# 26_LMS3_RX2_BB_ADC.net
KiCad netlist of a schematic drawn in Altium Designer
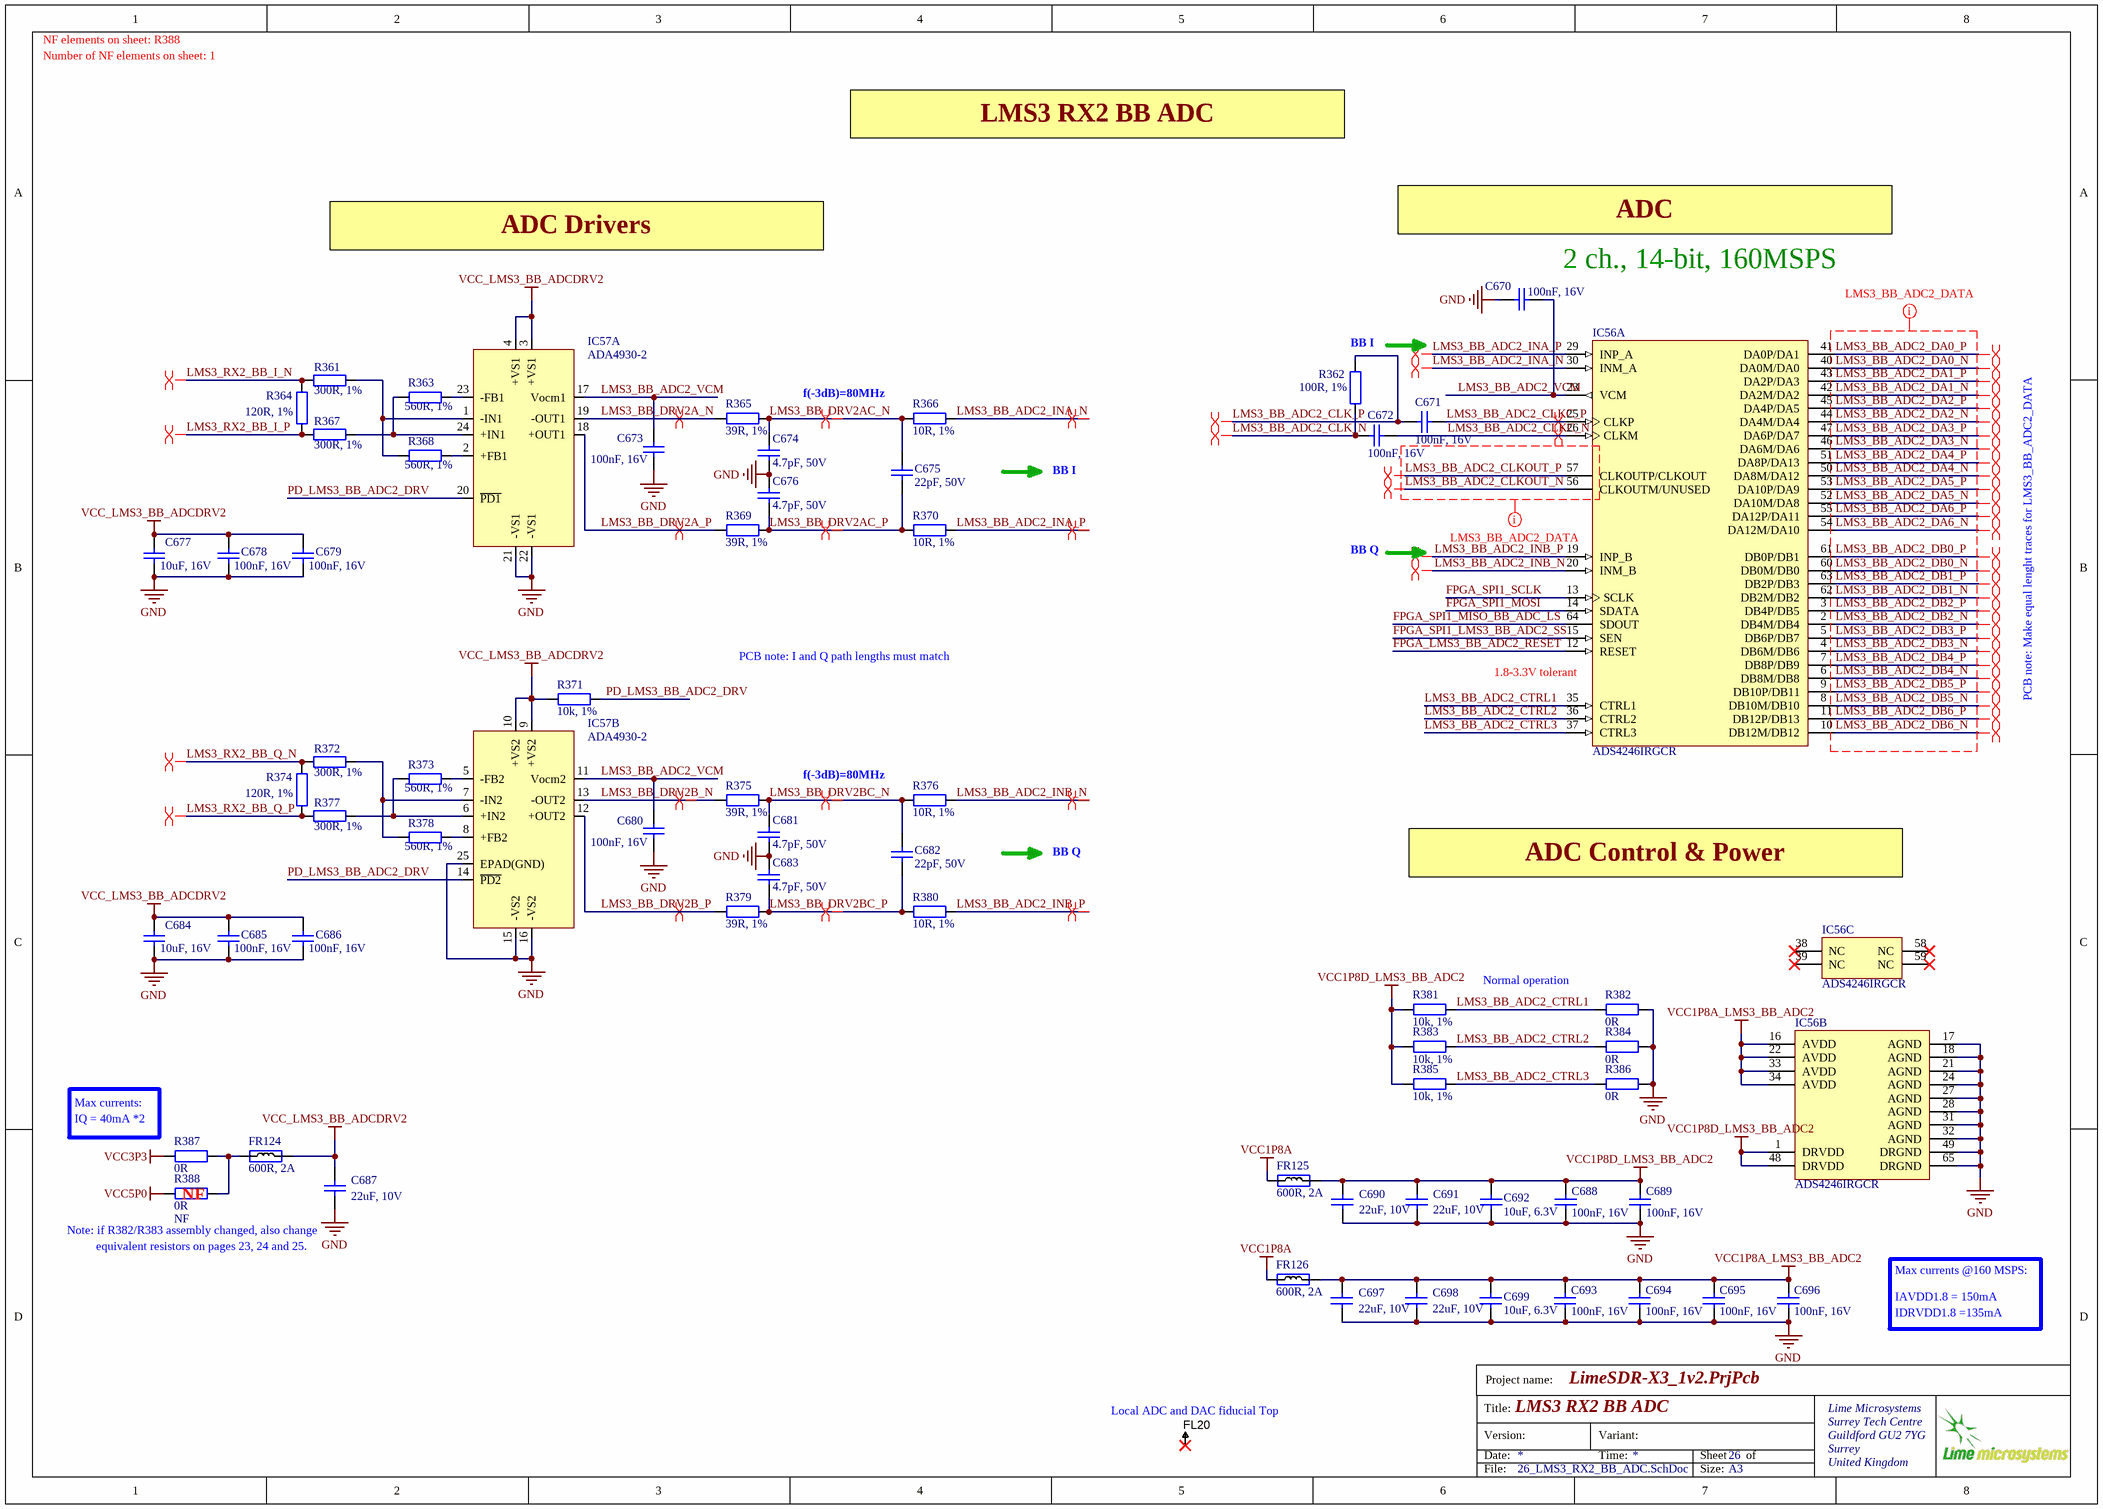
[diagram p0: 26_LMS3_RX2_BB_ADC.SchDoc]

(export (version "E")
  (design (tool "Eeschema 10.0.6"))
  (components
    (comp (ref "C670")
      (value "100nF, 16V")
      (footprint "CAP0402")
      (fields (field (name "TOLERANCE") "10 %") (field (name "MANUFACTURER") "Murata Electronics"))
      (libsource (lib "") (part "Cap_0603_3"))
    )
    (comp (ref "C671")
      (value "100nF, 16V")
      (footprint "CAP0402")
      (fields (field (name "TOLERANCE") "10 %") (field (name "MANUFACTURER") "Murata Electronics"))
      (libsource (lib "") (part "Cap_0603_3"))
    )
    (comp (ref "C672")
      (value "100nF, 16V")
      (footprint "CAP0402")
      (fields (field (name "TOLERANCE") "10 %") (field (name "MANUFACTURER") "Murata Electronics"))
      (libsource (lib "") (part "Cap_0603_5"))
    )
    (comp (ref "C673")
      (value "100nF, 16V")
      (footprint "CAP0402")
      (fields (field (name "TOLERANCE") "10 %") (field (name "MANUFACTURER") "Murata Electronics"))
      (libsource (lib "") (part "Cap_0603_5"))
    )
    (comp (ref "C674")
      (value "4.7pF, 50V")
      (footprint "CAP0402")
      (fields (field (name "MANUFACTURER") "MURATA"))
      (libsource (lib "LimeMicroAltiumLib_schLib") (part "Cap_0402"))
    )
    (comp (ref "C675")
      (value "22pF, 50V")
      (footprint "CAP0402")
      (fields (field (name "TOLERANCE") "±5%") (field (name "MANUFACTURER") "Yageo"))
      (libsource (lib "") (part "Cap_0402_1"))
    )
    (comp (ref "C676")
      (value "4.7pF, 50V")
      (footprint "CAP0402")
      (fields (field (name "MANUFACTURER") "MURATA"))
      (libsource (lib "LimeMicroAltiumLib_schLib") (part "Cap_0402"))
    )
    (comp (ref "C677")
      (value "10uF, 16V")
      (footprint "CAP0603")
      (fields (field (name "MANUFACTURER") "Yageo") (field (name "TOLERANCE") "±20%"))
      (libsource (lib "LimeMicroAltiumLib_schLib") (part "Cap_0603"))
    )
    (comp (ref "C678")
      (value "100nF, 16V")
      (footprint "CAP0402")
      (fields (field (name "TOLERANCE") "10 %") (field (name "MANUFACTURER") "Murata Electronics"))
      (libsource (lib "") (part "Cap_0603_5"))
    )
    (comp (ref "C679")
      (value "100nF, 16V")
      (footprint "CAP0402")
      (fields (field (name "TOLERANCE") "10 %") (field (name "MANUFACTURER") "Murata Electronics"))
      (libsource (lib "") (part "Cap_0603_5"))
    )
    (comp (ref "C680")
      (value "100nF, 16V")
      (footprint "CAP0402")
      (fields (field (name "TOLERANCE") "10 %") (field (name "MANUFACTURER") "Murata Electronics"))
      (libsource (lib "") (part "Cap_0603_6"))
    )
    (comp (ref "C681")
      (value "4.7pF, 50V")
      (footprint "CAP0402")
      (fields (field (name "MANUFACTURER") "MURATA"))
      (libsource (lib "LimeMicroAltiumLib_schLib") (part "Cap_0402"))
    )
    (comp (ref "C682")
      (value "22pF, 50V")
      (footprint "CAP0402")
      (fields (field (name "TOLERANCE") "±5%") (field (name "MANUFACTURER") "Yageo"))
      (libsource (lib "") (part "Cap_0402_1"))
    )
    (comp (ref "C683")
      (value "4.7pF, 50V")
      (footprint "CAP0402")
      (fields (field (name "MANUFACTURER") "MURATA"))
      (libsource (lib "LimeMicroAltiumLib_schLib") (part "Cap_0402"))
    )
    (comp (ref "C684")
      (value "10uF, 16V")
      (footprint "CAP0603")
      (fields (field (name "MANUFACTURER") "Yageo") (field (name "TOLERANCE") "±20%"))
      (libsource (lib "LimeMicroAltiumLib_schLib") (part "Cap_0603"))
    )
    (comp (ref "C685")
      (value "100nF, 16V")
      (footprint "CAP0402")
      (fields (field (name "TOLERANCE") "10 %") (field (name "MANUFACTURER") "Murata Electronics"))
      (libsource (lib "") (part "Cap_0603_5"))
    )
    (comp (ref "C686")
      (value "100nF, 16V")
      (footprint "CAP0402")
      (fields (field (name "TOLERANCE") "10 %") (field (name "MANUFACTURER") "Murata Electronics"))
      (libsource (lib "") (part "Cap_0603_5"))
    )
    (comp (ref "C687")
      (value "22uF, 10V")
      (footprint "CAP0603")
      (fields (field (name "TOLERANCE") "20 %") (field (name "MANUFACTURER") "TDK Corporation"))
      (libsource (lib "") (part "Cap_0603_2"))
    )
    (comp (ref "C688")
      (value "100nF, 16V")
      (footprint "CAP0402")
      (fields (field (name "TOLERANCE") "10 %") (field (name "MANUFACTURER") "Murata Electronics"))
      (libsource (lib "LimeFPGAboard_schLib") (part "Cap_0603"))
    )
    (comp (ref "C689")
      (value "100nF, 16V")
      (footprint "CAP0402")
      (fields (field (name "TOLERANCE") "10 %") (field (name "MANUFACTURER") "Murata Electronics"))
      (libsource (lib "LimeFPGAboard_schLib") (part "Cap_0603"))
    )
    (comp (ref "C690")
      (value "22uF, 10V")
      (footprint "CAP0603")
      (fields (field (name "TOLERANCE") "20 %") (field (name "MANUFACTURER") "TDK Corporation"))
      (libsource (lib "LimeFPGAboard_schLib") (part "Cap_0603"))
    )
    (comp (ref "C691")
      (value "22uF, 10V")
      (footprint "CAP0603")
      (fields (field (name "TOLERANCE") "20 %") (field (name "MANUFACTURER") "TDK Corporation"))
      (libsource (lib "LimeFPGAboard_schLib") (part "Cap_0603"))
    )
    (comp (ref "C692")
      (value "10uF, 6.3V")
      (footprint "CAP0603")
      (fields (field (name "TOLERANCE") "±20%") (field (name "MANUFACTURER") "Yageo"))
      (libsource (lib "") (part "Cap_0603_1"))
    )
    (comp (ref "C693")
      (value "100nF, 16V")
      (footprint "CAP0402")
      (fields (field (name "TOLERANCE") "10 %") (field (name "MANUFACTURER") "Murata Electronics"))
      (libsource (lib "") (part "Cap_0603_4"))
    )
    (comp (ref "C694")
      (value "100nF, 16V")
      (footprint "CAP0402")
      (fields (field (name "TOLERANCE") "10 %") (field (name "MANUFACTURER") "Murata Electronics"))
      (libsource (lib "") (part "Cap_0603_4"))
    )
    (comp (ref "C695")
      (value "100nF, 16V")
      (footprint "CAP0402")
      (fields (field (name "TOLERANCE") "10 %") (field (name "MANUFACTURER") "Murata Electronics"))
      (libsource (lib "") (part "Cap_0603_4"))
    )
    (comp (ref "C696")
      (value "100nF, 16V")
      (footprint "CAP0402")
      (fields (field (name "TOLERANCE") "10 %") (field (name "MANUFACTURER") "Murata Electronics"))
      (libsource (lib "") (part "Cap_0603_4"))
    )
    (comp (ref "C697")
      (value "22uF, 10V")
      (footprint "CAP0603")
      (fields (field (name "TOLERANCE") "20 %") (field (name "MANUFACTURER") "TDK Corporation"))
      (libsource (lib "") (part "Cap_0603_4"))
    )
    (comp (ref "C698")
      (value "22uF, 10V")
      (footprint "CAP0603")
      (fields (field (name "TOLERANCE") "20 %") (field (name "MANUFACTURER") "TDK Corporation"))
      (libsource (lib "") (part "Cap_0603_4"))
    )
    (comp (ref "C699")
      (value "10uF, 6.3V")
      (footprint "CAP0603")
      (fields (field (name "TOLERANCE") "±20%") (field (name "MANUFACTURER") "Yageo"))
      (libsource (lib "") (part "Cap_0603_7"))
    )
    (comp (ref "FL20")
      (value "Fiducial")
      (footprint "Fiducial_local")
      (libsource (lib "LimeMicroAltiumLib_schLib") (part "Fiducial"))
    )
    (comp (ref "FR124")
      (value "600R, 2A")
      (footprint "RES0805")
      (fields (field (name "MANUFACTURER") "TDK Corporation"))
      (libsource (lib "LimeMicroAltiumLib_schLib") (part "Ferrite"))
    )
    (comp (ref "FR125")
      (value "600R, 2A")
      (footprint "RES0805")
      (fields (field (name "MANUFACTURER") "TDK Corporation"))
      (libsource (lib "LimeFPGAboard_schLib") (part "Ferrite"))
    )
    (comp (ref "FR126")
      (value "600R, 2A")
      (footprint "RES0805")
      (fields (field (name "MANUFACTURER") "TDK Corporation"))
      (libsource (lib "LimeFPGAboard_schLib") (part "Ferrite"))
    )
    (comp (ref "IC56")
      (value "ADS4246IRGCR")
      (footprint "TI-RGC64-7400X7400TP_V")
      (description "14-Bit 160 MSPS Dual Low Power ADC, -40 to 85 degC, 64-pin QFN (RGC64), Green (RoHS & no Sb/Br)")
      (fields (field (name "MANUFACTURER") "Texas Instruments"))
      (libsource (lib "LimeMicroAltiumLib_schLib") (part "ADS4246IRGCR"))
    )
    (comp (ref "IC57")
      (value "ADA4930-2")
      (footprint "ADA4930-2_LFCSP-24")
      (fields (field (name "MANUFACTURER") "Analog Devices Inc."))
      (libsource (lib "LimeMicroAltiumLib_schLib") (part "ADA4930-2"))
    )
    (comp (ref "R361")
      (value "300R, 1%")
      (footprint "RES0402")
      (fields (field (name "TOLERANCE") "±1%") (field (name "MANUFACTURER") "Vishay Dale"))
      (libsource (lib "") (part "Res_0402_1"))
    )
    (comp (ref "R362")
      (value "100R, 1%")
      (footprint "RES0402")
      (fields (field (name "TOLERANCE") "±1%") (field (name "MANUFACTURER") "Stackpole Electronics Inc."))
      (libsource (lib "") (part "Res_0402_1"))
    )
    (comp (ref "R363")
      (value "560R, 1%")
      (footprint "RES0402")
      (fields (field (name "TOLERANCE") "±1%") (field (name "MANUFACTURER") "Vishay Dale"))
      (libsource (lib "") (part "Res_0402_1"))
    )
    (comp (ref "R364")
      (value "120R, 1%")
      (footprint "RES0402")
      (fields (field (name "MANUFACTURER") "Yageo") (field (name "TOLERANCE") "1%"))
      (libsource (lib "LimeFPGAboard_schLib") (part "Res_0402"))
    )
    (comp (ref "R365")
      (value "39R, 1%")
      (footprint "RES0402")
      (fields (field (name "MANUFACTURER") "Yageo") (field (name "TOLERANCE") "1%"))
      (libsource (lib "LimeMicroAltiumLib_schLib") (part "Res_0402"))
    )
    (comp (ref "R366")
      (value "10R, 1%")
      (footprint "RES0402")
      (fields (field (name "TOLERANCE") "1%"))
      (libsource (lib "LimeMicroAltiumLib_schLib") (part "Res_0402"))
    )
    (comp (ref "R367")
      (value "300R, 1%")
      (footprint "RES0402")
      (fields (field (name "TOLERANCE") "±1%") (field (name "MANUFACTURER") "Vishay Dale"))
      (libsource (lib "") (part "Res_0402_1"))
    )
    (comp (ref "R368")
      (value "560R, 1%")
      (footprint "RES0402")
      (fields (field (name "TOLERANCE") "±1%") (field (name "MANUFACTURER") "Vishay Dale"))
      (libsource (lib "") (part "Res_0402_1"))
    )
    (comp (ref "R369")
      (value "39R, 1%")
      (footprint "RES0402")
      (fields (field (name "MANUFACTURER") "Yageo") (field (name "TOLERANCE") "1%"))
      (libsource (lib "LimeMicroAltiumLib_schLib") (part "Res_0402"))
    )
    (comp (ref "R370")
      (value "10R, 1%")
      (footprint "RES0402")
      (fields (field (name "TOLERANCE") "1%"))
      (libsource (lib "LimeMicroAltiumLib_schLib") (part "Res_0402"))
    )
    (comp (ref "R371")
      (value "10k, 1%")
      (footprint "RES0402")
      (fields (field (name "MANUFACTURER") "Yageo") (field (name "TOLERANCE") "±1%"))
      (libsource (lib "LimeMicroAltiumLib_schLib") (part "Res_0402"))
    )
    (comp (ref "R372")
      (value "300R, 1%")
      (footprint "RES0402")
      (fields (field (name "TOLERANCE") "±1%") (field (name "MANUFACTURER") "Vishay Dale"))
      (libsource (lib "") (part "Res_0402_1"))
    )
    (comp (ref "R373")
      (value "560R, 1%")
      (footprint "RES0402")
      (fields (field (name "TOLERANCE") "±1%") (field (name "MANUFACTURER") "Vishay Dale"))
      (libsource (lib "") (part "Res_0402_1"))
    )
    (comp (ref "R374")
      (value "120R, 1%")
      (footprint "RES0402")
      (fields (field (name "MANUFACTURER") "Yageo") (field (name "TOLERANCE") "1%"))
      (libsource (lib "LimeFPGAboard_schLib") (part "Res_0402"))
    )
    (comp (ref "R375")
      (value "39R, 1%")
      (footprint "RES0402")
      (fields (field (name "MANUFACTURER") "Yageo") (field (name "TOLERANCE") "1%"))
      (libsource (lib "LimeMicroAltiumLib_schLib") (part "Res_0402"))
    )
    (comp (ref "R376")
      (value "10R, 1%")
      (footprint "RES0402")
      (fields (field (name "TOLERANCE") "1%"))
      (libsource (lib "LimeMicroAltiumLib_schLib") (part "Res_0402"))
    )
    (comp (ref "R377")
      (value "300R, 1%")
      (footprint "RES0402")
      (fields (field (name "TOLERANCE") "±1%") (field (name "MANUFACTURER") "Vishay Dale"))
      (libsource (lib "") (part "Res_0402_1"))
    )
    (comp (ref "R378")
      (value "560R, 1%")
      (footprint "RES0402")
      (fields (field (name "TOLERANCE") "±1%") (field (name "MANUFACTURER") "Vishay Dale"))
      (libsource (lib "") (part "Res_0402_1"))
    )
    (comp (ref "R379")
      (value "39R, 1%")
      (footprint "RES0402")
      (fields (field (name "MANUFACTURER") "Yageo") (field (name "TOLERANCE") "1%"))
      (libsource (lib "LimeMicroAltiumLib_schLib") (part "Res_0402"))
    )
    (comp (ref "R380")
      (value "10R, 1%")
      (footprint "RES0402")
      (fields (field (name "TOLERANCE") "1%"))
      (libsource (lib "LimeMicroAltiumLib_schLib") (part "Res_0402"))
    )
    (comp (ref "R381")
      (value "10k, 1%")
      (footprint "RES0402")
      (fields (field (name "MANUFACTURER") "Yageo") (field (name "TOLERANCE") "±1%"))
      (libsource (lib "LimeMicroAltiumLib_schLib") (part "Res_0402"))
    )
    (comp (ref "R382")
      (value "0R")
      (footprint "RES0402")
      (fields (field (name "MANUFACTURER") "Yageo"))
      (libsource (lib "") (part "Res_0402_1"))
    )
    (comp (ref "R383")
      (value "10k, 1%")
      (footprint "RES0402")
      (fields (field (name "MANUFACTURER") "Yageo") (field (name "TOLERANCE") "±1%"))
      (libsource (lib "LimeMicroAltiumLib_schLib") (part "Res_0402"))
    )
    (comp (ref "R384")
      (value "0R")
      (footprint "RES0402")
      (fields (field (name "MANUFACTURER") "Yageo"))
      (libsource (lib "") (part "Res_0402_1"))
    )
    (comp (ref "R385")
      (value "10k, 1%")
      (footprint "RES0402")
      (fields (field (name "MANUFACTURER") "Yageo") (field (name "TOLERANCE") "±1%"))
      (libsource (lib "LimeMicroAltiumLib_schLib") (part "Res_0402"))
    )
    (comp (ref "R386")
      (value "0R")
      (footprint "RES0402")
      (fields (field (name "MANUFACTURER") "Yageo"))
      (libsource (lib "") (part "Res_0402_1"))
    )
    (comp (ref "R387")
      (value "0R")
      (footprint "RES0402")
      (fields (field (name "MANUFACTURER") "Yageo") (field (name "TOLERANCE") "Jumper"))
      (libsource (lib "LimeMicroAltiumLib_schLib") (part "Res_0402"))
    )
    (comp (ref "R388")
      (value "0R")
      (footprint "RES0402")
      (fields
        (field (name "ASSEMBLY INFO") "NF")
        (field (name "MANUFACTURER") "Yageo")
        (field (name "TOLERANCE") "Jumper")
      )
      (libsource (lib "LimeMicroAltiumLib_schLib") (part "Res_0402"))
    )
  )
  (nets
    (net (code "1") (name "/FPGA_LMS3_BB_ADC2_RESET") (class "Default")
      (node (ref "IC56") (pin "12") (pinfunction "RESET_12") (pintype "input"))
    )
    (net (code "2") (name "/FPGA_SPI1_LMS3_BB_ADC2_SS") (class "Default")
      (node (ref "IC56") (pin "15") (pinfunction "SEN_15") (pintype "input"))
    )
    (net (code "3") (name "/FPGA_SPI1_MISO_BB_ADC_LS") (class "Default")
      (node (ref "IC56") (pin "64") (pinfunction "SDOUT_64") (pintype "tri_state"))
    )
    (net (code "4") (name "/FPGA_SPI1_MOSI") (class "Default")
      (node (ref "IC56") (pin "14") (pinfunction "SDATA_14") (pintype "input"))
    )
    (net (code "5") (name "/FPGA_SPI1_SCLK") (class "Default")
      (node (ref "IC56") (pin "13") (pinfunction "SCLK_13") (pintype "input"))
    )
    (net (code "6") (name "/LMS3_BB_ADC2_CLKC_N") (class "Default")
      (node (ref "C672") (pin "1") (pinfunction "1_1") (pintype "passive"))
      (node (ref "IC56") (pin "26") (pinfunction "CLKM_26") (pintype "input"))
    )
    (net (code "7") (name "/LMS3_BB_ADC2_CLKC_P") (class "Default")
      (node (ref "C671") (pin "1") (pinfunction "1_1") (pintype "passive"))
      (node (ref "IC56") (pin "25") (pinfunction "CLKP_25") (pintype "input"))
    )
    (net (code "8") (name "/LMS3_BB_ADC2_CLKOUT_N") (class "Default")
      (node (ref "IC56") (pin "56") (pinfunction "CLKOUTM/UNUSED_56") (pintype "tri_state"))
    )
    (net (code "9") (name "/LMS3_BB_ADC2_CLKOUT_P") (class "Default")
      (node (ref "IC56") (pin "57") (pinfunction "CLKOUTP/CLKOUT_57") (pintype "tri_state"))
    )
    (net (code "10") (name "/LMS3_BB_ADC2_CLK_N") (class "Default")
      (node (ref "C672") (pin "2") (pinfunction "2_2") (pintype "passive"))
      (node (ref "R362") (pin "1") (pinfunction "1_1") (pintype "passive"))
    )
    (net (code "11") (name "/LMS3_BB_ADC2_CLK_P") (class "Default")
      (node (ref "C671") (pin "2") (pinfunction "2_2") (pintype "passive"))
      (node (ref "R362") (pin "2") (pinfunction "2_2") (pintype "passive"))
    )
    (net (code "12") (name "/LMS3_BB_ADC2_CTRL1") (class "Default")
      (node (ref "IC56") (pin "35") (pinfunction "CTRL1_35") (pintype "input"))
      (node (ref "R381") (pin "1") (pinfunction "1_1") (pintype "passive"))
      (node (ref "R382") (pin "2") (pinfunction "2_2") (pintype "passive"))
    )
    (net (code "13") (name "/LMS3_BB_ADC2_CTRL2") (class "Default")
      (node (ref "IC56") (pin "36") (pinfunction "CTRL2_36") (pintype "input"))
      (node (ref "R383") (pin "1") (pinfunction "1_1") (pintype "passive"))
      (node (ref "R384") (pin "2") (pinfunction "2_2") (pintype "passive"))
    )
    (net (code "14") (name "/LMS3_BB_ADC2_CTRL3") (class "Default")
      (node (ref "IC56") (pin "37") (pinfunction "CTRL3_37") (pintype "input"))
      (node (ref "R385") (pin "1") (pinfunction "1_1") (pintype "passive"))
      (node (ref "R386") (pin "2") (pinfunction "2_2") (pintype "passive"))
    )
    (net (code "15") (name "/LMS3_BB_ADC2_DA0_N") (class "Default")
      (node (ref "IC56") (pin "40") (pinfunction "DA0M/DA0_40") (pintype "tri_state"))
    )
    (net (code "16") (name "/LMS3_BB_ADC2_DA0_P") (class "Default")
      (node (ref "IC56") (pin "41") (pinfunction "DA0P/DA1_41") (pintype "tri_state"))
    )
    (net (code "17") (name "/LMS3_BB_ADC2_DA1_N") (class "Default")
      (node (ref "IC56") (pin "42") (pinfunction "DA2M/DA2_42") (pintype "tri_state"))
    )
    (net (code "18") (name "/LMS3_BB_ADC2_DA1_P") (class "Default")
      (node (ref "IC56") (pin "43") (pinfunction "DA2P/DA3_43") (pintype "tri_state"))
    )
    (net (code "19") (name "/LMS3_BB_ADC2_DA2_N") (class "Default")
      (node (ref "IC56") (pin "44") (pinfunction "DA4M/DA4_44") (pintype "tri_state"))
    )
    (net (code "20") (name "/LMS3_BB_ADC2_DA2_P") (class "Default")
      (node (ref "IC56") (pin "45") (pinfunction "DA4P/DA5_45") (pintype "tri_state"))
    )
    (net (code "21") (name "/LMS3_BB_ADC2_DA3_N") (class "Default")
      (node (ref "IC56") (pin "46") (pinfunction "DA6M/DA6_46") (pintype "tri_state"))
    )
    (net (code "22") (name "/LMS3_BB_ADC2_DA3_P") (class "Default")
      (node (ref "IC56") (pin "47") (pinfunction "DA6P/DA7_47") (pintype "tri_state"))
    )
    (net (code "23") (name "/LMS3_BB_ADC2_DA4_N") (class "Default")
      (node (ref "IC56") (pin "50") (pinfunction "DA8M/DA12_50") (pintype "tri_state"))
    )
    (net (code "24") (name "/LMS3_BB_ADC2_DA4_P") (class "Default")
      (node (ref "IC56") (pin "51") (pinfunction "DA8P/DA13_51") (pintype "tri_state"))
    )
    (net (code "25") (name "/LMS3_BB_ADC2_DA5_N") (class "Default")
      (node (ref "IC56") (pin "52") (pinfunction "DA10M/DA8_52") (pintype "tri_state"))
    )
    (net (code "26") (name "/LMS3_BB_ADC2_DA5_P") (class "Default")
      (node (ref "IC56") (pin "53") (pinfunction "DA10P/DA9_53") (pintype "tri_state"))
    )
    (net (code "27") (name "/LMS3_BB_ADC2_DA6_N") (class "Default")
      (node (ref "IC56") (pin "54") (pinfunction "DA12M/DA10_54") (pintype "tri_state"))
    )
    (net (code "28") (name "/LMS3_BB_ADC2_DA6_P") (class "Default")
      (node (ref "IC56") (pin "55") (pinfunction "DA12P/DA11_55") (pintype "tri_state"))
    )
    (net (code "29") (name "/LMS3_BB_ADC2_DB0_N") (class "Default")
      (node (ref "IC56") (pin "60") (pinfunction "DB0M/DB0_60") (pintype "tri_state"))
    )
    (net (code "30") (name "/LMS3_BB_ADC2_DB0_P") (class "Default")
      (node (ref "IC56") (pin "61") (pinfunction "DB0P/DB1_61") (pintype "tri_state"))
    )
    (net (code "31") (name "/LMS3_BB_ADC2_DB1_N") (class "Default")
      (node (ref "IC56") (pin "62") (pinfunction "DB2M/DB2_62") (pintype "tri_state"))
    )
    (net (code "32") (name "/LMS3_BB_ADC2_DB1_P") (class "Default")
      (node (ref "IC56") (pin "63") (pinfunction "DB2P/DB3_63") (pintype "tri_state"))
    )
    (net (code "33") (name "/LMS3_BB_ADC2_DB2_N") (class "Default")
      (node (ref "IC56") (pin "2") (pinfunction "DB4M/DB4_2") (pintype "tri_state"))
    )
    (net (code "34") (name "/LMS3_BB_ADC2_DB2_P") (class "Default")
      (node (ref "IC56") (pin "3") (pinfunction "DB4P/DB5_3") (pintype "tri_state"))
    )
    (net (code "35") (name "/LMS3_BB_ADC2_DB3_N") (class "Default")
      (node (ref "IC56") (pin "4") (pinfunction "DB6M/DB6_4") (pintype "tri_state"))
    )
    (net (code "36") (name "/LMS3_BB_ADC2_DB3_P") (class "Default")
      (node (ref "IC56") (pin "5") (pinfunction "DB6P/DB7_5") (pintype "tri_state"))
    )
    (net (code "37") (name "/LMS3_BB_ADC2_DB4_N") (class "Default")
      (node (ref "IC56") (pin "6") (pinfunction "DB8M/DB8_6") (pintype "tri_state"))
    )
    (net (code "38") (name "/LMS3_BB_ADC2_DB4_P") (class "Default")
      (node (ref "IC56") (pin "7") (pinfunction "DB8P/DB9_7") (pintype "tri_state"))
    )
    (net (code "39") (name "/LMS3_BB_ADC2_DB5_N") (class "Default")
      (node (ref "IC56") (pin "8") (pinfunction "DB10M/DB10_8") (pintype "tri_state"))
    )
    (net (code "40") (name "/LMS3_BB_ADC2_DB5_P") (class "Default")
      (node (ref "IC56") (pin "9") (pinfunction "DB10P/DB11_9") (pintype "tri_state"))
    )
    (net (code "41") (name "/LMS3_BB_ADC2_DB6_N") (class "Default")
      (node (ref "IC56") (pin "10") (pinfunction "DB12M/DB12_10") (pintype "tri_state"))
    )
    (net (code "42") (name "/LMS3_BB_ADC2_DB6_P") (class "Default")
      (node (ref "IC56") (pin "11") (pinfunction "DB12P/DB13_11") (pintype "tri_state"))
    )
    (net (code "43") (name "/LMS3_BB_ADC2_INA_N") (class "Default")
      (node (ref "IC56") (pin "30") (pinfunction "INM_A_30") (pintype "input"))
      (node (ref "R366") (pin "1") (pinfunction "1_1") (pintype "passive"))
    )
    (net (code "44") (name "/LMS3_BB_ADC2_INA_P") (class "Default")
      (node (ref "IC56") (pin "29") (pinfunction "INP_A_29") (pintype "input"))
      (node (ref "R370") (pin "1") (pinfunction "1_1") (pintype "passive"))
    )
    (net (code "45") (name "/LMS3_BB_ADC2_INB_N") (class "Default")
      (node (ref "IC56") (pin "20") (pinfunction "INM_B_20") (pintype "input"))
      (node (ref "R376") (pin "1") (pinfunction "1_1") (pintype "passive"))
    )
    (net (code "46") (name "/LMS3_BB_ADC2_INB_P") (class "Default")
      (node (ref "IC56") (pin "19") (pinfunction "INP_B_19") (pintype "input"))
      (node (ref "R380") (pin "1") (pinfunction "1_1") (pintype "passive"))
    )
    (net (code "47") (name "/LMS3_BB_ADC2_VCM") (class "Default")
      (node (ref "C670") (pin "2") (pinfunction "2_2") (pintype "passive"))
      (node (ref "C673") (pin "1") (pinfunction "1_1") (pintype "passive"))
      (node (ref "C680") (pin "1") (pinfunction "1_1") (pintype "passive"))
      (node (ref "IC56") (pin "23") (pinfunction "VCM_23") (pintype "output"))
      (node (ref "IC57") (pin "11") (pinfunction "Vocm2_11") (pintype "input"))
      (node (ref "IC57") (pin "17") (pinfunction "Vocm1_17") (pintype "input"))
    )
    (net (code "48") (name "/LMS3_BB_DRV2AC_N") (class "Default")
      (node (ref "C674") (pin "1") (pinfunction "1_1") (pintype "passive"))
      (node (ref "C675") (pin "1") (pinfunction "1_1") (pintype "passive"))
      (node (ref "R365") (pin "1") (pinfunction "1_1") (pintype "passive"))
      (node (ref "R366") (pin "2") (pinfunction "2_2") (pintype "passive"))
    )
    (net (code "49") (name "/LMS3_BB_DRV2AC_P") (class "Default")
      (node (ref "C675") (pin "2") (pinfunction "2_2") (pintype "passive"))
      (node (ref "C676") (pin "2") (pinfunction "2_2") (pintype "passive"))
      (node (ref "R369") (pin "1") (pinfunction "1_1") (pintype "passive"))
      (node (ref "R370") (pin "2") (pinfunction "2_2") (pintype "passive"))
    )
    (net (code "50") (name "/LMS3_BB_DRV2A_N") (class "Default")
      (node (ref "IC57") (pin "19") (pinfunction "-OUT1_19") (pintype "output"))
      (node (ref "R365") (pin "2") (pinfunction "2_2") (pintype "passive"))
    )
    (net (code "51") (name "/LMS3_BB_DRV2A_P") (class "Default")
      (node (ref "IC57") (pin "18") (pinfunction "+OUT1_18") (pintype "output"))
      (node (ref "R369") (pin "2") (pinfunction "2_2") (pintype "passive"))
    )
    (net (code "52") (name "/LMS3_BB_DRV2BC_N") (class "Default")
      (node (ref "C681") (pin "1") (pinfunction "1_1") (pintype "passive"))
      (node (ref "C682") (pin "1") (pinfunction "1_1") (pintype "passive"))
      (node (ref "R375") (pin "1") (pinfunction "1_1") (pintype "passive"))
      (node (ref "R376") (pin "2") (pinfunction "2_2") (pintype "passive"))
    )
    (net (code "53") (name "/LMS3_BB_DRV2BC_P") (class "Default")
      (node (ref "C682") (pin "2") (pinfunction "2_2") (pintype "passive"))
      (node (ref "C683") (pin "2") (pinfunction "2_2") (pintype "passive"))
      (node (ref "R379") (pin "1") (pinfunction "1_1") (pintype "passive"))
      (node (ref "R380") (pin "2") (pinfunction "2_2") (pintype "passive"))
    )
    (net (code "54") (name "/LMS3_BB_DRV2B_N") (class "Default")
      (node (ref "IC57") (pin "13") (pinfunction "-OUT2_13") (pintype "output"))
      (node (ref "R375") (pin "2") (pinfunction "2_2") (pintype "passive"))
    )
    (net (code "55") (name "/LMS3_BB_DRV2B_P") (class "Default")
      (node (ref "IC57") (pin "12") (pinfunction "+OUT2_12") (pintype "output"))
      (node (ref "R379") (pin "2") (pinfunction "2_2") (pintype "passive"))
    )
    (net (code "56") (name "/LMS3_RX2_BB_I_N") (class "Default")
      (node (ref "R361") (pin "2") (pinfunction "2_2") (pintype "passive"))
      (node (ref "R364") (pin "2") (pinfunction "2_2") (pintype "passive"))
    )
    (net (code "57") (name "/LMS3_RX2_BB_I_P") (class "Default")
      (node (ref "R364") (pin "1") (pinfunction "1_1") (pintype "passive"))
      (node (ref "R367") (pin "2") (pinfunction "2_2") (pintype "passive"))
    )
    (net (code "58") (name "/LMS3_RX2_BB_Q_N") (class "Default")
      (node (ref "R372") (pin "2") (pinfunction "2_2") (pintype "passive"))
      (node (ref "R374") (pin "2") (pinfunction "2_2") (pintype "passive"))
    )
    (net (code "59") (name "/LMS3_RX2_BB_Q_P") (class "Default")
      (node (ref "R374") (pin "1") (pinfunction "1_1") (pintype "passive"))
      (node (ref "R377") (pin "2") (pinfunction "2_2") (pintype "passive"))
    )
    (net (code "60") (name "/PD_LMS3_BB_ADC2_DRV") (class "Default")
      (node (ref "IC57") (pin "14") (pinfunction "~{PD2}_14") (pintype "input"))
      (node (ref "IC57") (pin "20") (pinfunction "~{PD1}_20") (pintype "input"))
      (node (ref "R371") (pin "1") (pinfunction "1_1") (pintype "passive"))
    )
    (net (code "61") (name "GND") (class "Default")
      (node (ref "C670") (pin "1") (pinfunction "1_1") (pintype "passive"))
      (node (ref "C673") (pin "2") (pinfunction "2_2") (pintype "passive"))
      (node (ref "C674") (pin "2") (pinfunction "2_2") (pintype "passive"))
      (node (ref "C676") (pin "1") (pinfunction "1_1") (pintype "passive"))
      (node (ref "C677") (pin "1") (pinfunction "1_1") (pintype "passive"))
      (node (ref "C678") (pin "2") (pinfunction "2_2") (pintype "passive"))
      (node (ref "C679") (pin "2") (pinfunction "2_2") (pintype "passive"))
      (node (ref "C680") (pin "2") (pinfunction "2_2") (pintype "passive"))
      (node (ref "C681") (pin "2") (pinfunction "2_2") (pintype "passive"))
      (node (ref "C683") (pin "1") (pinfunction "1_1") (pintype "passive"))
      (node (ref "C684") (pin "1") (pinfunction "1_1") (pintype "passive"))
      (node (ref "C685") (pin "2") (pinfunction "2_2") (pintype "passive"))
      (node (ref "C686") (pin "2") (pinfunction "2_2") (pintype "passive"))
      (node (ref "C687") (pin "1") (pinfunction "1_1") (pintype "passive"))
      (node (ref "C688") (pin "1") (pinfunction "1_1") (pintype "passive"))
      (node (ref "C689") (pin "1") (pinfunction "1_1") (pintype "passive"))
      (node (ref "C690") (pin "1") (pinfunction "1_1") (pintype "passive"))
      (node (ref "C691") (pin "1") (pinfunction "1_1") (pintype "passive"))
      (node (ref "C692") (pin "2") (pinfunction "2_2") (pintype "passive"))
      (node (ref "C693") (pin "1") (pinfunction "1_1") (pintype "passive"))
      (node (ref "C694") (pin "1") (pinfunction "1_1") (pintype "passive"))
      (node (ref "C695") (pin "1") (pinfunction "1_1") (pintype "passive"))
      (node (ref "C696") (pin "1") (pinfunction "1_1") (pintype "passive"))
      (node (ref "C697") (pin "1") (pinfunction "1_1") (pintype "passive"))
      (node (ref "C698") (pin "1") (pinfunction "1_1") (pintype "passive"))
      (node (ref "C699") (pin "2") (pinfunction "2_2") (pintype "passive"))
      (node (ref "IC56") (pin "17") (pinfunction "AGND_17") (pintype "power_in"))
      (node (ref "IC56") (pin "18") (pinfunction "AGND_18") (pintype "power_in"))
      (node (ref "IC56") (pin "21") (pinfunction "AGND_21") (pintype "power_in"))
      (node (ref "IC56") (pin "24") (pinfunction "AGND_24") (pintype "power_in"))
      (node (ref "IC56") (pin "27") (pinfunction "AGND_27") (pintype "power_in"))
      (node (ref "IC56") (pin "28") (pinfunction "AGND_28") (pintype "power_in"))
      (node (ref "IC56") (pin "31") (pinfunction "AGND_31") (pintype "power_in"))
      (node (ref "IC56") (pin "32") (pinfunction "AGND_32") (pintype "power_in"))
      (node (ref "IC56") (pin "49") (pinfunction "DRGND_49") (pintype "power_in"))
      (node (ref "IC56") (pin "65") (pinfunction "DRGND_65") (pintype "power_in"))
      (node (ref "IC57") (pin "15") (pinfunction "-VS2_15") (pintype "power_in"))
      (node (ref "IC57") (pin "16") (pinfunction "-VS2_16") (pintype "power_in"))
      (node (ref "IC57") (pin "21") (pinfunction "-VS1_21") (pintype "power_in"))
      (node (ref "IC57") (pin "22") (pinfunction "-VS1_22") (pintype "power_in"))
      (node (ref "IC57") (pin "25") (pinfunction "EPAD(GND)_25") (pintype "passive"))
      (node (ref "R382") (pin "1") (pinfunction "1_1") (pintype "passive"))
      (node (ref "R384") (pin "1") (pinfunction "1_1") (pintype "passive"))
      (node (ref "R386") (pin "1") (pinfunction "1_1") (pintype "passive"))
    )
    (net (code "62") (name "Net-(FR124-Pad1)") (class "Default")
      (node (ref "FR124") (pin "1") (pinfunction "1_1") (pintype "passive"))
      (node (ref "R387") (pin "1") (pinfunction "1_1") (pintype "passive"))
      (node (ref "R388") (pin "1") (pinfunction "1_1") (pintype "passive"))
    )
    (net (code "63") (name "Net-(IC57A-+FB1)") (class "Default")
      (node (ref "IC57") (pin "2") (pinfunction "+FB1_2") (pintype "output"))
      (node (ref "R368") (pin "1") (pinfunction "1_1") (pintype "passive"))
    )
    (net (code "64") (name "Net-(IC57A-+IN1)") (class "Default")
      (node (ref "IC57") (pin "24") (pinfunction "+IN1_24") (pintype "input"))
      (node (ref "R363") (pin "2") (pinfunction "2_2") (pintype "passive"))
      (node (ref "R367") (pin "1") (pinfunction "1_1") (pintype "passive"))
    )
    (net (code "65") (name "Net-(IC57A--FB1)") (class "Default")
      (node (ref "IC57") (pin "23") (pinfunction "-FB1_23") (pintype "output"))
      (node (ref "R363") (pin "1") (pinfunction "1_1") (pintype "passive"))
    )
    (net (code "66") (name "Net-(IC57A--IN1)") (class "Default")
      (node (ref "IC57") (pin "1") (pinfunction "-IN1_1") (pintype "input"))
      (node (ref "R361") (pin "1") (pinfunction "1_1") (pintype "passive"))
      (node (ref "R368") (pin "2") (pinfunction "2_2") (pintype "passive"))
    )
    (net (code "67") (name "Net-(IC57B-+FB2)") (class "Default")
      (node (ref "IC57") (pin "8") (pinfunction "+FB2_8") (pintype "output"))
      (node (ref "R378") (pin "1") (pinfunction "1_1") (pintype "passive"))
    )
    (net (code "68") (name "Net-(IC57B-+IN2)") (class "Default")
      (node (ref "IC57") (pin "6") (pinfunction "+IN2_6") (pintype "input"))
      (node (ref "R373") (pin "2") (pinfunction "2_2") (pintype "passive"))
      (node (ref "R377") (pin "1") (pinfunction "1_1") (pintype "passive"))
    )
    (net (code "69") (name "Net-(IC57B--FB2)") (class "Default")
      (node (ref "IC57") (pin "5") (pinfunction "-FB2_5") (pintype "output"))
      (node (ref "R373") (pin "1") (pinfunction "1_1") (pintype "passive"))
    )
    (net (code "70") (name "Net-(IC57B--IN2)") (class "Default")
      (node (ref "IC57") (pin "7") (pinfunction "-IN2_7") (pintype "input"))
      (node (ref "R372") (pin "1") (pinfunction "1_1") (pintype "passive"))
      (node (ref "R378") (pin "2") (pinfunction "2_2") (pintype "passive"))
    )
    (net (code "71") (name "VCC1P8A") (class "Default")
      (node (ref "FR125") (pin "1") (pinfunction "1_1") (pintype "passive"))
      (node (ref "FR126") (pin "1") (pinfunction "1_1") (pintype "passive"))
    )
    (net (code "72") (name "VCC1P8A_LMS3_BB_ADC2") (class "Default")
      (node (ref "C693") (pin "2") (pinfunction "2_2") (pintype "passive"))
      (node (ref "C694") (pin "2") (pinfunction "2_2") (pintype "passive"))
      (node (ref "C695") (pin "2") (pinfunction "2_2") (pintype "passive"))
      (node (ref "C696") (pin "2") (pinfunction "2_2") (pintype "passive"))
      (node (ref "C697") (pin "2") (pinfunction "2_2") (pintype "passive"))
      (node (ref "C698") (pin "2") (pinfunction "2_2") (pintype "passive"))
      (node (ref "C699") (pin "1") (pinfunction "1_1") (pintype "passive"))
      (node (ref "FR126") (pin "2") (pinfunction "2_2") (pintype "passive"))
      (node (ref "IC56") (pin "16") (pinfunction "AVDD_16") (pintype "power_in"))
      (node (ref "IC56") (pin "22") (pinfunction "AVDD_22") (pintype "power_in"))
      (node (ref "IC56") (pin "33") (pinfunction "AVDD_33") (pintype "power_in"))
      (node (ref "IC56") (pin "34") (pinfunction "AVDD_34") (pintype "power_in"))
    )
    (net (code "73") (name "VCC1P8D_LMS3_BB_ADC2") (class "Default")
      (node (ref "C688") (pin "2") (pinfunction "2_2") (pintype "passive"))
      (node (ref "C689") (pin "2") (pinfunction "2_2") (pintype "passive"))
      (node (ref "C690") (pin "2") (pinfunction "2_2") (pintype "passive"))
      (node (ref "C691") (pin "2") (pinfunction "2_2") (pintype "passive"))
      (node (ref "C692") (pin "1") (pinfunction "1_1") (pintype "passive"))
      (node (ref "FR125") (pin "2") (pinfunction "2_2") (pintype "passive"))
      (node (ref "IC56") (pin "1") (pinfunction "DRVDD_1") (pintype "power_in"))
      (node (ref "IC56") (pin "48") (pinfunction "DRVDD_48") (pintype "power_in"))
      (node (ref "R381") (pin "2") (pinfunction "2_2") (pintype "passive"))
      (node (ref "R383") (pin "2") (pinfunction "2_2") (pintype "passive"))
      (node (ref "R385") (pin "2") (pinfunction "2_2") (pintype "passive"))
    )
    (net (code "74") (name "VCC3P3") (class "Default")
      (node (ref "R387") (pin "2") (pinfunction "2_2") (pintype "passive"))
    )
    (net (code "75") (name "VCC5P0") (class "Default")
      (node (ref "R388") (pin "2") (pinfunction "2_2") (pintype "passive"))
    )
    (net (code "76") (name "VCC_LMS3_BB_ADCDRV2") (class "Default")
      (node (ref "C677") (pin "2") (pinfunction "2_2") (pintype "passive"))
      (node (ref "C678") (pin "1") (pinfunction "1_1") (pintype "passive"))
      (node (ref "C679") (pin "1") (pinfunction "1_1") (pintype "passive"))
      (node (ref "C684") (pin "2") (pinfunction "2_2") (pintype "passive"))
      (node (ref "C685") (pin "1") (pinfunction "1_1") (pintype "passive"))
      (node (ref "C686") (pin "1") (pinfunction "1_1") (pintype "passive"))
      (node (ref "C687") (pin "2") (pinfunction "2_2") (pintype "passive"))
      (node (ref "FR124") (pin "2") (pinfunction "2_2") (pintype "passive"))
      (node (ref "IC57") (pin "10") (pinfunction "+VS2_10") (pintype "power_in"))
      (node (ref "IC57") (pin "3") (pinfunction "+VS1_3") (pintype "power_in"))
      (node (ref "IC57") (pin "4") (pinfunction "+VS1_4") (pintype "power_in"))
      (node (ref "IC57") (pin "9") (pinfunction "+VS2_9") (pintype "power_in"))
      (node (ref "R371") (pin "2") (pinfunction "2_2") (pintype "passive"))
    )
    (net (code "77") (name "unconnected-(FL20-Pad1)") (class "Default")
      (node (ref "FL20") (pin "1") (pintype "passive+no_connect"))
    )
    (net (code "78") (name "unconnected-(IC56C-NC-Pad38)") (class "Default")
      (node (ref "IC56") (pin "38") (pinfunction "NC_38") (pintype "passive+no_connect"))
    )
    (net (code "79") (name "unconnected-(IC56C-NC-Pad39)") (class "Default")
      (node (ref "IC56") (pin "39") (pinfunction "NC_39") (pintype "passive+no_connect"))
    )
    (net (code "80") (name "unconnected-(IC56C-NC-Pad58)") (class "Default")
      (node (ref "IC56") (pin "58") (pinfunction "NC_58") (pintype "passive+no_connect"))
    )
    (net (code "81") (name "unconnected-(IC56C-NC-Pad59)") (class "Default")
      (node (ref "IC56") (pin "59") (pinfunction "NC_59") (pintype "passive+no_connect"))
    )
  )
)
